# overall_pcb_1_1.net
KiCad netlist of a schematic drawn in EAGLE
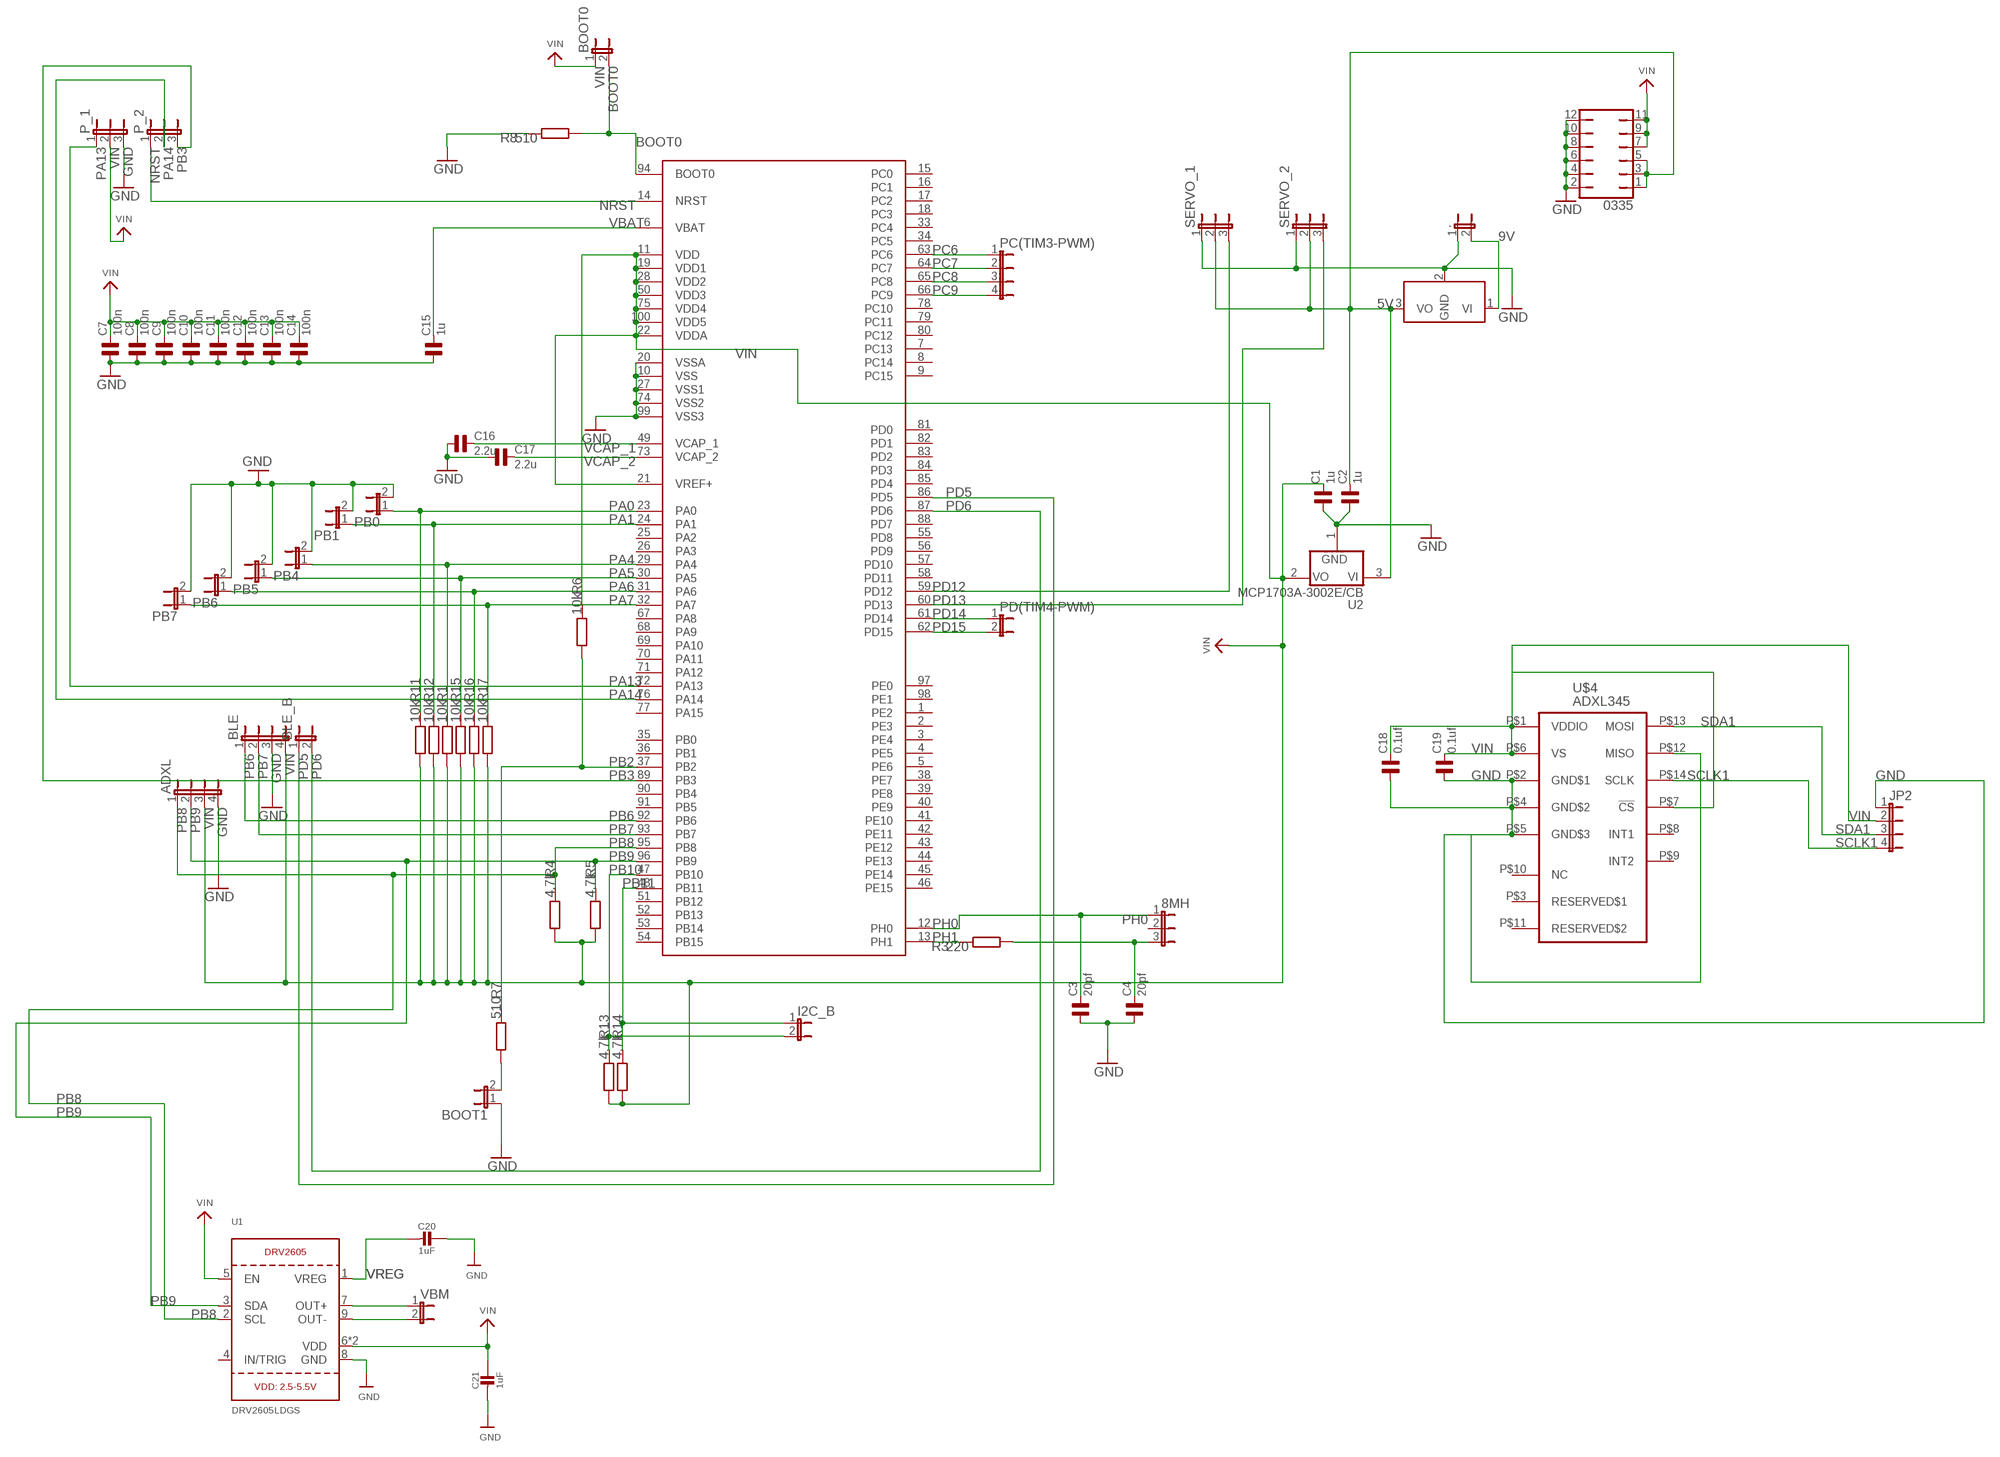
[diagram p0: schematic, sheet 1]

(export (version "E")
  (design (tool "Eeschema 10.0.6"))
  (components
    (comp (ref ".")
      (value "JP1E")
      (footprint "eagle-import:JP1")
      (libsource (lib "eagle-import") (part "JP1E"))
    )
    (comp (ref "8MH")
      (value "JP2E")
      (footprint "eagle-import:JP2")
      (libsource (lib "eagle-import") (part "JP2E"))
    )
    (comp (ref "0335")
      (value "JP6Q")
      (footprint "eagle-import:JP6Q")
      (libsource (lib "eagle-import") (part "JP6Q"))
    )
    (comp (ref "ADXL")
      (value "JP4E")
      (footprint "eagle-import:JP4")
      (libsource (lib "eagle-import") (part "JP4E"))
    )
    (comp (ref "BLE")
      (value "JP4E")
      (footprint "eagle-import:JP4")
      (libsource (lib "eagle-import") (part "JP4E"))
    )
    (comp (ref "BLE_B")
      (value "JP1E")
      (footprint "eagle-import:JP1")
      (libsource (lib "eagle-import") (part "JP1E"))
    )
    (comp (ref "BOOT0")
      (value "JP1E")
      (footprint "eagle-import:JP1")
      (libsource (lib "eagle-import") (part "JP1E"))
    )
    (comp (ref "BOOT1")
      (value "JP1E")
      (footprint "eagle-import:JP1")
      (libsource (lib "eagle-import") (part "JP1E"))
    )
    (comp (ref "C1")
      (value "1u")
      (footprint "eagle-import:0805")
      (libsource (lib "eagle-import") (part "C0805"))
    )
    (comp (ref "C2")
      (value "1u")
      (footprint "eagle-import:0805")
      (libsource (lib "eagle-import") (part "C0805"))
    )
    (comp (ref "C3")
      (value "20pf")
      (footprint "eagle-import:0805")
      (libsource (lib "eagle-import") (part "C0805"))
    )
    (comp (ref "C4")
      (value "20pf")
      (footprint "eagle-import:0805")
      (libsource (lib "eagle-import") (part "C0805"))
    )
    (comp (ref "C7")
      (value "100n")
      (footprint "eagle-import:0805")
      (libsource (lib "eagle-import") (part "C0805"))
    )
    (comp (ref "C8")
      (value "100n")
      (footprint "eagle-import:0805")
      (libsource (lib "eagle-import") (part "C0805"))
    )
    (comp (ref "C9")
      (value "100n")
      (footprint "eagle-import:0805")
      (libsource (lib "eagle-import") (part "C0805"))
    )
    (comp (ref "C10")
      (value "100n")
      (footprint "eagle-import:0805")
      (libsource (lib "eagle-import") (part "C0805"))
    )
    (comp (ref "C11")
      (value "100n")
      (footprint "eagle-import:0805")
      (libsource (lib "eagle-import") (part "C0805"))
    )
    (comp (ref "C12")
      (value "100n")
      (footprint "eagle-import:0805")
      (libsource (lib "eagle-import") (part "C0805"))
    )
    (comp (ref "C13")
      (value "100n")
      (footprint "eagle-import:0805")
      (libsource (lib "eagle-import") (part "C0805"))
    )
    (comp (ref "C14")
      (value "100n")
      (footprint "eagle-import:0805")
      (libsource (lib "eagle-import") (part "C0805"))
    )
    (comp (ref "C15")
      (value "1u")
      (footprint "eagle-import:0805")
      (libsource (lib "eagle-import") (part "C0805"))
    )
    (comp (ref "C16")
      (value "2.2u")
      (footprint "eagle-import:0805")
      (libsource (lib "eagle-import") (part "C0805"))
    )
    (comp (ref "C17")
      (value "2.2u")
      (footprint "eagle-import:0805")
      (libsource (lib "eagle-import") (part "C0805"))
    )
    (comp (ref "C18")
      (value "0.1uf")
      (footprint "eagle-import:0805")
      (libsource (lib "eagle-import") (part "C0805"))
    )
    (comp (ref "C19")
      (value "0.1uf")
      (footprint "eagle-import:0805")
      (libsource (lib "eagle-import") (part "C0805"))
    )
    (comp (ref "C20")
      (value "1uF")
      (footprint "eagle-import:0805-NO")
      (libsource (lib "eagle-import") (part "CAP_CERAMIC0805-NOOUTLINE"))
    )
    (comp (ref "C21")
      (value "1uF")
      (footprint "eagle-import:0805-NO")
      (libsource (lib "eagle-import") (part "CAP_CERAMIC0805-NOOUTLINE"))
    )
    (comp (ref "I2C_B")
      (value "JP1E")
      (footprint "eagle-import:JP1")
      (libsource (lib "eagle-import") (part "JP1E"))
    )
    (comp (ref "JP2")
      (value "JP4E")
      (footprint "eagle-import:JP4")
      (libsource (lib "eagle-import") (part "JP4E"))
    )
    (comp (ref "PB0")
      (value "JP1E")
      (footprint "eagle-import:JP1")
      (libsource (lib "eagle-import") (part "JP1E"))
    )
    (comp (ref "PB1")
      (value "JP1E")
      (footprint "eagle-import:JP1")
      (libsource (lib "eagle-import") (part "JP1E"))
    )
    (comp (ref "PB4")
      (value "JP1E")
      (footprint "eagle-import:JP1")
      (libsource (lib "eagle-import") (part "JP1E"))
    )
    (comp (ref "PB5")
      (value "JP1E")
      (footprint "eagle-import:JP1")
      (libsource (lib "eagle-import") (part "JP1E"))
    )
    (comp (ref "PB6")
      (value "JP1E")
      (footprint "eagle-import:JP1")
      (libsource (lib "eagle-import") (part "JP1E"))
    )
    (comp (ref "PB7")
      (value "JP1E")
      (footprint "eagle-import:JP1")
      (libsource (lib "eagle-import") (part "JP1E"))
    )
    (comp (ref "PC(TIM3-PWM)")
      (value "JP4E")
      (footprint "eagle-import:JP4")
      (libsource (lib "eagle-import") (part "JP4E"))
    )
    (comp (ref "PD(TIM4-PWM)")
      (value "JP1E")
      (footprint "eagle-import:JP1")
      (libsource (lib "eagle-import") (part "JP1E"))
    )
    (comp (ref "P_1")
      (value "JP2E")
      (footprint "eagle-import:JP2")
      (libsource (lib "eagle-import") (part "JP2E"))
    )
    (comp (ref "P_2")
      (value "JP2E")
      (footprint "eagle-import:JP2")
      (libsource (lib "eagle-import") (part "JP2E"))
    )
    (comp (ref "R1")
      (value "10k")
      (footprint "eagle-import:R0805")
      (libsource (lib "eagle-import") (part "R-EU_R0805"))
    )
    (comp (ref "R3")
      (value "220")
      (footprint "eagle-import:R0805")
      (libsource (lib "eagle-import") (part "R-EU_R0805"))
    )
    (comp (ref "R4")
      (value "4.7k")
      (footprint "eagle-import:R0805")
      (libsource (lib "eagle-import") (part "R-EU_R0805"))
    )
    (comp (ref "R5")
      (value "4.7k")
      (footprint "eagle-import:R0805")
      (libsource (lib "eagle-import") (part "R-EU_R0805"))
    )
    (comp (ref "R6")
      (value "10k")
      (footprint "eagle-import:R0805")
      (libsource (lib "eagle-import") (part "R-EU_R0805"))
    )
    (comp (ref "R7")
      (value "510")
      (footprint "eagle-import:R0805")
      (libsource (lib "eagle-import") (part "R-EU_R0805"))
    )
    (comp (ref "R8")
      (value "510")
      (footprint "eagle-import:R0805")
      (libsource (lib "eagle-import") (part "R-EU_R0805"))
    )
    (comp (ref "R11")
      (value "10k")
      (footprint "eagle-import:R0805")
      (libsource (lib "eagle-import") (part "R-EU_R0805"))
    )
    (comp (ref "R12")
      (value "10k")
      (footprint "eagle-import:R0805")
      (libsource (lib "eagle-import") (part "R-EU_R0805"))
    )
    (comp (ref "R13")
      (value "4.7k")
      (footprint "eagle-import:R0805")
      (libsource (lib "eagle-import") (part "R-EU_R0805"))
    )
    (comp (ref "R14")
      (value "4.7k")
      (footprint "eagle-import:R0805")
      (libsource (lib "eagle-import") (part "R-EU_R0805"))
    )
    (comp (ref "R15")
      (value "10k")
      (footprint "eagle-import:R0805")
      (libsource (lib "eagle-import") (part "R-EU_R0805"))
    )
    (comp (ref "R16")
      (value "10k")
      (footprint "eagle-import:R0805")
      (libsource (lib "eagle-import") (part "R-EU_R0805"))
    )
    (comp (ref "R17")
      (value "10k")
      (footprint "eagle-import:R0805")
      (libsource (lib "eagle-import") (part "R-EU_R0805"))
    )
    (comp (ref "SERVO_1")
      (value "JP2E")
      (footprint "eagle-import:JP2")
      (libsource (lib "eagle-import") (part "JP2E"))
    )
    (comp (ref "SERVO_2")
      (value "JP2E")
      (footprint "eagle-import:JP2")
      (libsource (lib "eagle-import") (part "JP2E"))
    )
    (comp (ref "U$1")
      (value "STM32F40XSTM32D40X")
      (footprint "eagle-import:LQFP100")
      (libsource (lib "eagle-import") (part "STM32F40XSTM32D40X"))
    )
    (comp (ref "U$2")
      (value "DCDC_OKI-78SR")
      (footprint "eagle-import:OKI-78SRH")
      (libsource (lib "eagle-import") (part "DCDC_OKI-78SR"))
    )
    (comp (ref "U$4")
      (value "ADXL345")
      (footprint "eagle-import:LGA14")
      (libsource (lib "eagle-import") (part "ADXL345"))
    )
    (comp (ref "U1")
      (value "DRV2605LDGS")
      (footprint "eagle-import:PSOP10")
      (libsource (lib "eagle-import") (part "DRV2605_SOP"))
    )
    (comp (ref "U2")
      (value "MCP1703A-3002E/CB")
      (footprint "eagle-import:SOT23A_MICROCHIP_CB")
      (libsource (lib "eagle-import") (part "MCP170302E/CBA-30"))
    )
    (comp (ref "VBM")
      (value "JP1E")
      (footprint "eagle-import:JP1")
      (libsource (lib "eagle-import") (part "JP1E"))
    )
  )
  (nets
    (net (code "1") (name "/5V") (class "Default")
      (node (ref "0335") (pin "1") (pinfunction "1_1") (pintype "passive"))
      (node (ref "0335") (pin "3") (pinfunction "3_3") (pintype "passive"))
      (node (ref "0335") (pin "5") (pinfunction "5_5") (pintype "passive"))
      (node (ref "C2") (pin "2") (pinfunction "2_2") (pintype "passive"))
      (node (ref "SERVO_1") (pin "2") (pinfunction "2_2") (pintype "passive"))
      (node (ref "SERVO_2") (pin "2") (pinfunction "2_2") (pintype "passive"))
      (node (ref "U$2") (pin "3") (pinfunction "VO_3") (pintype "bidirectional"))
      (node (ref "U2") (pin "3") (pinfunction "VI_3") (pintype "power_in"))
    )
    (net (code "2") (name "/9V") (class "Default")
      (node (ref ".") (pin "2") (pinfunction "2_2") (pintype "passive"))
      (node (ref "U$2") (pin "1") (pinfunction "VI_1") (pintype "bidirectional"))
    )
    (net (code "3") (name "/BOOT0") (class "Default")
      (node (ref "BOOT0") (pin "2") (pinfunction "2_2") (pintype "passive"))
      (node (ref "R8") (pin "1") (pinfunction "1_1") (pintype "passive"))
      (node (ref "U$1") (pin "94") (pinfunction "BOOT0_94") (pintype "bidirectional"))
    )
    (net (code "4") (name "/NRST") (class "Default")
      (node (ref "P_2") (pin "1") (pinfunction "1_1") (pintype "passive"))
      (node (ref "U$1") (pin "14") (pinfunction "NRST_14") (pintype "bidirectional"))
    )
    (net (code "5") (name "/PA0") (class "Default")
      (node (ref "PB0") (pin "1") (pinfunction "1_1") (pintype "passive"))
      (node (ref "R11") (pin "2") (pinfunction "2_2") (pintype "passive"))
      (node (ref "U$1") (pin "23") (pinfunction "PA0_23") (pintype "bidirectional"))
    )
    (net (code "6") (name "/PA1") (class "Default")
      (node (ref "PB1") (pin "1") (pinfunction "1_1") (pintype "passive"))
      (node (ref "R12") (pin "2") (pinfunction "2_2") (pintype "passive"))
      (node (ref "U$1") (pin "24") (pinfunction "PA1_24") (pintype "bidirectional"))
    )
    (net (code "7") (name "/PA4") (class "Default")
      (node (ref "PB4") (pin "1") (pinfunction "1_1") (pintype "passive"))
      (node (ref "R1") (pin "2") (pinfunction "2_2") (pintype "passive"))
      (node (ref "U$1") (pin "29") (pinfunction "PA4_29") (pintype "bidirectional"))
    )
    (net (code "8") (name "/PA5") (class "Default")
      (node (ref "PB5") (pin "1") (pinfunction "1_1") (pintype "passive"))
      (node (ref "R15") (pin "2") (pinfunction "2_2") (pintype "passive"))
      (node (ref "U$1") (pin "30") (pinfunction "PA5_30") (pintype "bidirectional"))
    )
    (net (code "9") (name "/PA6") (class "Default")
      (node (ref "PB6") (pin "1") (pinfunction "1_1") (pintype "passive"))
      (node (ref "R16") (pin "2") (pinfunction "2_2") (pintype "passive"))
      (node (ref "U$1") (pin "31") (pinfunction "PA6_31") (pintype "bidirectional"))
    )
    (net (code "10") (name "/PA7") (class "Default")
      (node (ref "PB7") (pin "1") (pinfunction "1_1") (pintype "passive"))
      (node (ref "R17") (pin "2") (pinfunction "2_2") (pintype "passive"))
      (node (ref "U$1") (pin "32") (pinfunction "PA7_32") (pintype "bidirectional"))
    )
    (net (code "11") (name "/PA13") (class "Default")
      (node (ref "P_1") (pin "1") (pinfunction "1_1") (pintype "passive"))
      (node (ref "U$1") (pin "72") (pinfunction "PA13_72") (pintype "bidirectional"))
    )
    (net (code "12") (name "/PA14") (class "Default")
      (node (ref "P_2") (pin "2") (pinfunction "2_2") (pintype "passive"))
      (node (ref "U$1") (pin "76") (pinfunction "PA14_76") (pintype "bidirectional"))
    )
    (net (code "13") (name "/PB2") (class "Default")
      (node (ref "R6") (pin "1") (pinfunction "1_1") (pintype "passive"))
      (node (ref "R7") (pin "2") (pinfunction "2_2") (pintype "passive"))
      (node (ref "U$1") (pin "37") (pinfunction "PB2_37") (pintype "bidirectional"))
    )
    (net (code "14") (name "/PB3") (class "Default")
      (node (ref "P_2") (pin "3") (pinfunction "3_3") (pintype "passive"))
      (node (ref "U$1") (pin "89") (pinfunction "PB3_89") (pintype "bidirectional"))
    )
    (net (code "15") (name "/PB6") (class "Default")
      (node (ref "BLE") (pin "1") (pinfunction "1_1") (pintype "passive"))
      (node (ref "U$1") (pin "92") (pinfunction "PB6_92") (pintype "bidirectional"))
    )
    (net (code "16") (name "/PB7") (class "Default")
      (node (ref "BLE") (pin "2") (pinfunction "2_2") (pintype "passive"))
      (node (ref "U$1") (pin "93") (pinfunction "PB7_93") (pintype "bidirectional"))
    )
    (net (code "17") (name "/PB8") (class "Default")
      (node (ref "ADXL") (pin "1") (pinfunction "1_1") (pintype "passive"))
      (node (ref "R4") (pin "2") (pinfunction "2_2") (pintype "passive"))
      (node (ref "U$1") (pin "95") (pinfunction "PB8_95") (pintype "bidirectional"))
      (node (ref "U1") (pin "2") (pinfunction "SCL_2") (pintype "input"))
    )
    (net (code "18") (name "/PB9") (class "Default")
      (node (ref "ADXL") (pin "2") (pinfunction "2_2") (pintype "passive"))
      (node (ref "R5") (pin "2") (pinfunction "2_2") (pintype "passive"))
      (node (ref "U$1") (pin "96") (pinfunction "PB9_96") (pintype "bidirectional"))
      (node (ref "U1") (pin "3") (pinfunction "SDA_3") (pintype "bidirectional"))
    )
    (net (code "19") (name "/PB10") (class "Default")
      (node (ref "I2C_B") (pin "2") (pinfunction "2_2") (pintype "passive"))
      (node (ref "R13") (pin "2") (pinfunction "2_2") (pintype "passive"))
      (node (ref "U$1") (pin "47") (pinfunction "PB10_47") (pintype "bidirectional"))
    )
    (net (code "20") (name "/PB11") (class "Default")
      (node (ref "I2C_B") (pin "1") (pinfunction "1_1") (pintype "passive"))
      (node (ref "R14") (pin "2") (pinfunction "2_2") (pintype "passive"))
      (node (ref "U$1") (pin "48") (pinfunction "PB11_48") (pintype "bidirectional"))
    )
    (net (code "21") (name "/PC6") (class "Default")
      (node (ref "PC(TIM3-PWM)") (pin "1") (pinfunction "1_1") (pintype "passive"))
      (node (ref "U$1") (pin "63") (pinfunction "PC6_63") (pintype "bidirectional"))
    )
    (net (code "22") (name "/PC7") (class "Default")
      (node (ref "PC(TIM3-PWM)") (pin "2") (pinfunction "2_2") (pintype "passive"))
      (node (ref "U$1") (pin "64") (pinfunction "PC7_64") (pintype "bidirectional"))
    )
    (net (code "23") (name "/PC8") (class "Default")
      (node (ref "PC(TIM3-PWM)") (pin "3") (pinfunction "3_3") (pintype "passive"))
      (node (ref "U$1") (pin "65") (pinfunction "PC8_65") (pintype "bidirectional"))
    )
    (net (code "24") (name "/PC9") (class "Default")
      (node (ref "PC(TIM3-PWM)") (pin "4") (pinfunction "4_4") (pintype "passive"))
      (node (ref "U$1") (pin "66") (pinfunction "PC9_66") (pintype "bidirectional"))
    )
    (net (code "25") (name "/PD5") (class "Default")
      (node (ref "BLE_B") (pin "1") (pinfunction "1_1") (pintype "passive"))
      (node (ref "U$1") (pin "86") (pinfunction "PD5_86") (pintype "bidirectional"))
    )
    (net (code "26") (name "/PD6") (class "Default")
      (node (ref "BLE_B") (pin "2") (pinfunction "2_2") (pintype "passive"))
      (node (ref "U$1") (pin "87") (pinfunction "PD6_87") (pintype "bidirectional"))
    )
    (net (code "27") (name "/PD12") (class "Default")
      (node (ref "SERVO_1") (pin "3") (pinfunction "3_3") (pintype "passive"))
      (node (ref "U$1") (pin "59") (pinfunction "PD12_59") (pintype "bidirectional"))
    )
    (net (code "28") (name "/PD13") (class "Default")
      (node (ref "SERVO_2") (pin "3") (pinfunction "3_3") (pintype "passive"))
      (node (ref "U$1") (pin "60") (pinfunction "PD13_60") (pintype "bidirectional"))
    )
    (net (code "29") (name "/PD14") (class "Default")
      (node (ref "PD(TIM4-PWM)") (pin "1") (pinfunction "1_1") (pintype "passive"))
      (node (ref "U$1") (pin "61") (pinfunction "PD14_61") (pintype "bidirectional"))
    )
    (net (code "30") (name "/PD15") (class "Default")
      (node (ref "PD(TIM4-PWM)") (pin "2") (pinfunction "2_2") (pintype "passive"))
      (node (ref "U$1") (pin "62") (pinfunction "PD15_62") (pintype "bidirectional"))
    )
    (net (code "31") (name "/PH0") (class "Default")
      (node (ref "8MH") (pin "1") (pinfunction "1_1") (pintype "passive"))
      (node (ref "C3") (pin "2") (pinfunction "2_2") (pintype "passive"))
      (node (ref "U$1") (pin "12") (pinfunction "PH0_12") (pintype "bidirectional"))
    )
    (net (code "32") (name "/PH1") (class "Default")
      (node (ref "R3") (pin "2") (pinfunction "2_2") (pintype "passive"))
      (node (ref "U$1") (pin "13") (pinfunction "PH1_13") (pintype "bidirectional"))
    )
    (net (code "33") (name "/SCLK1") (class "Default")
      (node (ref "JP2") (pin "4") (pinfunction "4_4") (pintype "passive"))
      (node (ref "U$4") (pin "P$14") (pinfunction "SCLK_P$14") (pintype "input"))
    )
    (net (code "34") (name "/SDA1") (class "Default")
      (node (ref "JP2") (pin "3") (pinfunction "3_3") (pintype "passive"))
      (node (ref "U$4") (pin "P$13") (pinfunction "MOSI_P$13") (pintype "input"))
    )
    (net (code "35") (name "/VBAT") (class "Default")
      (node (ref "C15") (pin "2") (pinfunction "2_2") (pintype "passive"))
      (node (ref "U$1") (pin "6") (pinfunction "VBAT_6") (pintype "bidirectional"))
    )
    (net (code "36") (name "/VCAP_1") (class "Default")
      (node (ref "C16") (pin "2") (pinfunction "2_2") (pintype "passive"))
      (node (ref "U$1") (pin "49") (pinfunction "VCAP_1_49") (pintype "bidirectional"))
    )
    (net (code "37") (name "/VCAP_2") (class "Default")
      (node (ref "C17") (pin "2") (pinfunction "2_2") (pintype "passive"))
      (node (ref "U$1") (pin "73") (pinfunction "VCAP_2_73") (pintype "bidirectional"))
    )
    (net (code "38") (name "/VREG") (class "Default")
      (node (ref "C20") (pin "2") (pinfunction "2_2") (pintype "passive"))
      (node (ref "U1") (pin "1") (pinfunction "VREG_1") (pintype "output"))
    )
    (net (code "39") (name "GND") (class "Default")
      (node (ref ".") (pin "1") (pinfunction "1_1") (pintype "passive"))
      (node (ref "0335") (pin "10") (pinfunction "10_10") (pintype "passive"))
      (node (ref "0335") (pin "12") (pinfunction "12_12") (pintype "passive"))
      (node (ref "0335") (pin "2") (pinfunction "2_2") (pintype "passive"))
      (node (ref "0335") (pin "4") (pinfunction "4_4") (pintype "passive"))
      (node (ref "0335") (pin "6") (pinfunction "6_6") (pintype "passive"))
      (node (ref "0335") (pin "8") (pinfunction "8_8") (pintype "passive"))
      (node (ref "ADXL") (pin "4") (pinfunction "4_4") (pintype "passive"))
      (node (ref "BLE") (pin "3") (pinfunction "3_3") (pintype "passive"))
      (node (ref "BOOT1") (pin "1") (pinfunction "1_1") (pintype "passive"))
      (node (ref "C1") (pin "1") (pinfunction "1_1") (pintype "passive"))
      (node (ref "C10") (pin "1") (pinfunction "1_1") (pintype "passive"))
      (node (ref "C11") (pin "1") (pinfunction "1_1") (pintype "passive"))
      (node (ref "C12") (pin "1") (pinfunction "1_1") (pintype "passive"))
      (node (ref "C13") (pin "1") (pinfunction "1_1") (pintype "passive"))
      (node (ref "C14") (pin "1") (pinfunction "1_1") (pintype "passive"))
      (node (ref "C15") (pin "1") (pinfunction "1_1") (pintype "passive"))
      (node (ref "C16") (pin "1") (pinfunction "1_1") (pintype "passive"))
      (node (ref "C17") (pin "1") (pinfunction "1_1") (pintype "passive"))
      (node (ref "C18") (pin "1") (pinfunction "1_1") (pintype "passive"))
      (node (ref "C19") (pin "1") (pinfunction "1_1") (pintype "passive"))
      (node (ref "C2") (pin "1") (pinfunction "1_1") (pintype "passive"))
      (node (ref "C20") (pin "1") (pinfunction "1_1") (pintype "passive"))
      (node (ref "C21") (pin "2") (pinfunction "2_2") (pintype "passive"))
      (node (ref "C3") (pin "1") (pinfunction "1_1") (pintype "passive"))
      (node (ref "C4") (pin "1") (pinfunction "1_1") (pintype "passive"))
      (node (ref "C7") (pin "1") (pinfunction "1_1") (pintype "passive"))
      (node (ref "C8") (pin "1") (pinfunction "1_1") (pintype "passive"))
      (node (ref "C9") (pin "1") (pinfunction "1_1") (pintype "passive"))
      (node (ref "JP2") (pin "1") (pinfunction "1_1") (pintype "passive"))
      (node (ref "PB0") (pin "2") (pinfunction "2_2") (pintype "passive"))
      (node (ref "PB1") (pin "2") (pinfunction "2_2") (pintype "passive"))
      (node (ref "PB4") (pin "2") (pinfunction "2_2") (pintype "passive"))
      (node (ref "PB5") (pin "2") (pinfunction "2_2") (pintype "passive"))
      (node (ref "PB6") (pin "2") (pinfunction "2_2") (pintype "passive"))
      (node (ref "PB7") (pin "2") (pinfunction "2_2") (pintype "passive"))
      (node (ref "P_1") (pin "3") (pinfunction "3_3") (pintype "passive"))
      (node (ref "R8") (pin "2") (pinfunction "2_2") (pintype "passive"))
      (node (ref "SERVO_1") (pin "1") (pinfunction "1_1") (pintype "passive"))
      (node (ref "SERVO_2") (pin "1") (pinfunction "1_1") (pintype "passive"))
      (node (ref "U$1") (pin "10") (pinfunction "VSS_10") (pintype "bidirectional"))
      (node (ref "U$1") (pin "20") (pinfunction "VSSA_20") (pintype "bidirectional"))
      (node (ref "U$1") (pin "27") (pinfunction "VSS1_27") (pintype "bidirectional"))
      (node (ref "U$1") (pin "74") (pinfunction "VSS2_74") (pintype "bidirectional"))
      (node (ref "U$1") (pin "99") (pinfunction "VSS3_99") (pintype "bidirectional"))
      (node (ref "U$2") (pin "2") (pinfunction "GND_2") (pintype "bidirectional"))
      (node (ref "U$4") (pin "P$12") (pinfunction "MISO_P$12") (pintype "output"))
      (node (ref "U$4") (pin "P$2") (pinfunction "GND$1_P$2") (pintype "power_in"))
      (node (ref "U$4") (pin "P$4") (pinfunction "GND$2_P$4") (pintype "power_in"))
      (node (ref "U$4") (pin "P$5") (pinfunction "GND$3_P$5") (pintype "power_in"))
      (node (ref "U1") (pin "8") (pinfunction "GND_8") (pintype "power_in"))
      (node (ref "U2") (pin "1") (pinfunction "GND_1") (pintype "power_in"))
    )
    (net (code "40") (name "Net-(8MH-Pad3)") (class "Default")
      (node (ref "8MH") (pin "3") (pinfunction "3_3") (pintype "passive"))
      (node (ref "C4") (pin "2") (pinfunction "2_2") (pintype "passive"))
      (node (ref "R3") (pin "1") (pinfunction "1_1") (pintype "passive"))
    )
    (net (code "41") (name "Net-(BOOT1-Pad2)") (class "Default")
      (node (ref "BOOT1") (pin "2") (pinfunction "2_2") (pintype "passive"))
      (node (ref "R7") (pin "1") (pinfunction "1_1") (pintype "passive"))
    )
    (net (code "42") (name "Net-(U1-OUT+)") (class "Default")
      (node (ref "U1") (pin "7") (pinfunction "OUT+_7") (pintype "output"))
      (node (ref "VBM") (pin "1") (pinfunction "1_1") (pintype "passive"))
    )
    (net (code "43") (name "Net-(U1-OUT-)") (class "Default")
      (node (ref "U1") (pin "9") (pinfunction "OUT-_9") (pintype "output"))
      (node (ref "VBM") (pin "2") (pinfunction "2_2") (pintype "passive"))
    )
    (net (code "44") (name "VIN") (class "Default")
      (node (ref "0335") (pin "11") (pinfunction "11_11") (pintype "passive"))
      (node (ref "0335") (pin "7") (pinfunction "7_7") (pintype "passive"))
      (node (ref "0335") (pin "9") (pinfunction "9_9") (pintype "passive"))
      (node (ref "ADXL") (pin "3") (pinfunction "3_3") (pintype "passive"))
      (node (ref "BLE") (pin "4") (pinfunction "4_4") (pintype "passive"))
      (node (ref "BOOT0") (pin "1") (pinfunction "1_1") (pintype "passive"))
      (node (ref "C1") (pin "2") (pinfunction "2_2") (pintype "passive"))
      (node (ref "C10") (pin "2") (pinfunction "2_2") (pintype "passive"))
      (node (ref "C11") (pin "2") (pinfunction "2_2") (pintype "passive"))
      (node (ref "C12") (pin "2") (pinfunction "2_2") (pintype "passive"))
      (node (ref "C13") (pin "2") (pinfunction "2_2") (pintype "passive"))
      (node (ref "C14") (pin "2") (pinfunction "2_2") (pintype "passive"))
      (node (ref "C18") (pin "2") (pinfunction "2_2") (pintype "passive"))
      (node (ref "C19") (pin "2") (pinfunction "2_2") (pintype "passive"))
      (node (ref "C21") (pin "1") (pinfunction "1_1") (pintype "passive"))
      (node (ref "C7") (pin "2") (pinfunction "2_2") (pintype "passive"))
      (node (ref "C8") (pin "2") (pinfunction "2_2") (pintype "passive"))
      (node (ref "C9") (pin "2") (pinfunction "2_2") (pintype "passive"))
      (node (ref "JP2") (pin "2") (pinfunction "2_2") (pintype "passive"))
      (node (ref "P_1") (pin "2") (pinfunction "2_2") (pintype "passive"))
      (node (ref "R1") (pin "1") (pinfunction "1_1") (pintype "passive"))
      (node (ref "R11") (pin "1") (pinfunction "1_1") (pintype "passive"))
      (node (ref "R12") (pin "1") (pinfunction "1_1") (pintype "passive"))
      (node (ref "R13") (pin "1") (pinfunction "1_1") (pintype "passive"))
      (node (ref "R14") (pin "1") (pinfunction "1_1") (pintype "passive"))
      (node (ref "R15") (pin "1") (pinfunction "1_1") (pintype "passive"))
      (node (ref "R16") (pin "1") (pinfunction "1_1") (pintype "passive"))
      (node (ref "R17") (pin "1") (pinfunction "1_1") (pintype "passive"))
      (node (ref "R4") (pin "1") (pinfunction "1_1") (pintype "passive"))
      (node (ref "R5") (pin "1") (pinfunction "1_1") (pintype "passive"))
      (node (ref "R6") (pin "2") (pinfunction "2_2") (pintype "passive"))
      (node (ref "U$1") (pin "100") (pinfunction "VDD5_100") (pintype "bidirectional"))
      (node (ref "U$1") (pin "11") (pinfunction "VDD_11") (pintype "bidirectional"))
      (node (ref "U$1") (pin "19") (pinfunction "VDD1_19") (pintype "bidirectional"))
      (node (ref "U$1") (pin "21") (pinfunction "VREF+_21") (pintype "bidirectional"))
      (node (ref "U$1") (pin "22") (pinfunction "VDDA_22") (pintype "bidirectional"))
      (node (ref "U$1") (pin "28") (pinfunction "VDD2_28") (pintype "bidirectional"))
      (node (ref "U$1") (pin "50") (pinfunction "VDD3_50") (pintype "bidirectional"))
      (node (ref "U$1") (pin "75") (pinfunction "VDD4_75") (pintype "bidirectional"))
      (node (ref "U$4") (pin "P$1") (pinfunction "VDDIO_P$1") (pintype "power_in"))
      (node (ref "U$4") (pin "P$6") (pinfunction "VS_P$6") (pintype "power_in"))
      (node (ref "U$4") (pin "P$7") (pinfunction "~{CS}_P$7") (pintype "input"))
      (node (ref "U1") (pin "10") (pinfunction "VDD_10") (pintype "power_in"))
      (node (ref "U1") (pin "5") (pinfunction "EN_5") (pintype "input"))
      (node (ref "U1") (pin "6") (pinfunction "VDD_6") (pintype "power_in"))
      (node (ref "U2") (pin "2") (pinfunction "VO_2") (pintype "passive"))
    )
    (net (code "45") (name "unconnected-(8MH-Pad2)") (class "Default")
      (node (ref "8MH") (pin "2") (pinfunction "2_2") (pintype "passive"))
    )
    (net (code "46") (name "unconnected-(U$1-PA2-Pad25)") (class "Default")
      (node (ref "U$1") (pin "25") (pinfunction "PA2_25") (pintype "bidirectional"))
    )
    (net (code "47") (name "unconnected-(U$1-PA3-Pad26)") (class "Default")
      (node (ref "U$1") (pin "26") (pinfunction "PA3_26") (pintype "bidirectional"))
    )
    (net (code "48") (name "unconnected-(U$1-PA8-Pad67)") (class "Default")
      (node (ref "U$1") (pin "67") (pinfunction "PA8_67") (pintype "bidirectional"))
    )
    (net (code "49") (name "unconnected-(U$1-PA9-Pad68)") (class "Default")
      (node (ref "U$1") (pin "68") (pinfunction "PA9_68") (pintype "bidirectional"))
    )
    (net (code "50") (name "unconnected-(U$1-PA10-Pad69)") (class "Default")
      (node (ref "U$1") (pin "69") (pinfunction "PA10_69") (pintype "bidirectional"))
    )
    (net (code "51") (name "unconnected-(U$1-PA11-Pad70)") (class "Default")
      (node (ref "U$1") (pin "70") (pinfunction "PA11_70") (pintype "bidirectional"))
    )
    (net (code "52") (name "unconnected-(U$1-PA12-Pad71)") (class "Default")
      (node (ref "U$1") (pin "71") (pinfunction "PA12_71") (pintype "bidirectional"))
    )
    (net (code "53") (name "unconnected-(U$1-PA15-Pad77)") (class "Default")
      (node (ref "U$1") (pin "77") (pinfunction "PA15_77") (pintype "bidirectional"))
    )
    (net (code "54") (name "unconnected-(U$1-PB0-Pad35)") (class "Default")
      (node (ref "U$1") (pin "35") (pinfunction "PB0_35") (pintype "bidirectional"))
    )
    (net (code "55") (name "unconnected-(U$1-PB1-Pad36)") (class "Default")
      (node (ref "U$1") (pin "36") (pinfunction "PB1_36") (pintype "bidirectional"))
    )
    (net (code "56") (name "unconnected-(U$1-PB4-Pad90)") (class "Default")
      (node (ref "U$1") (pin "90") (pinfunction "PB4_90") (pintype "bidirectional"))
    )
    (net (code "57") (name "unconnected-(U$1-PB5-Pad91)") (class "Default")
      (node (ref "U$1") (pin "91") (pinfunction "PB5_91") (pintype "bidirectional"))
    )
    (net (code "58") (name "unconnected-(U$1-PB12-Pad51)") (class "Default")
      (node (ref "U$1") (pin "51") (pinfunction "PB12_51") (pintype "bidirectional"))
    )
    (net (code "59") (name "unconnected-(U$1-PB13-Pad52)") (class "Default")
      (node (ref "U$1") (pin "52") (pinfunction "PB13_52") (pintype "bidirectional"))
    )
    (net (code "60") (name "unconnected-(U$1-PB14-Pad53)") (class "Default")
      (node (ref "U$1") (pin "53") (pinfunction "PB14_53") (pintype "bidirectional"))
    )
    (net (code "61") (name "unconnected-(U$1-PB15-Pad54)") (class "Default")
      (node (ref "U$1") (pin "54") (pinfunction "PB15_54") (pintype "bidirectional"))
    )
    (net (code "62") (name "unconnected-(U$1-PC0-Pad15)") (class "Default")
      (node (ref "U$1") (pin "15") (pinfunction "PC0_15") (pintype "bidirectional"))
    )
    (net (code "63") (name "unconnected-(U$1-PC1-Pad16)") (class "Default")
      (node (ref "U$1") (pin "16") (pinfunction "PC1_16") (pintype "bidirectional"))
    )
    (net (code "64") (name "unconnected-(U$1-PC2-Pad17)") (class "Default")
      (node (ref "U$1") (pin "17") (pinfunction "PC2_17") (pintype "bidirectional"))
    )
    (net (code "65") (name "unconnected-(U$1-PC3-Pad18)") (class "Default")
      (node (ref "U$1") (pin "18") (pinfunction "PC3_18") (pintype "bidirectional"))
    )
    (net (code "66") (name "unconnected-(U$1-PC4-Pad33)") (class "Default")
      (node (ref "U$1") (pin "33") (pinfunction "PC4_33") (pintype "bidirectional"))
    )
    (net (code "67") (name "unconnected-(U$1-PC5-Pad34)") (class "Default")
      (node (ref "U$1") (pin "34") (pinfunction "PC5_34") (pintype "bidirectional"))
    )
    (net (code "68") (name "unconnected-(U$1-PC10-Pad78)") (class "Default")
      (node (ref "U$1") (pin "78") (pinfunction "PC10_78") (pintype "bidirectional"))
    )
    (net (code "69") (name "unconnected-(U$1-PC11-Pad79)") (class "Default")
      (node (ref "U$1") (pin "79") (pinfunction "PC11_79") (pintype "bidirectional"))
    )
    (net (code "70") (name "unconnected-(U$1-PC12-Pad80)") (class "Default")
      (node (ref "U$1") (pin "80") (pinfunction "PC12_80") (pintype "bidirectional"))
    )
    (net (code "71") (name "unconnected-(U$1-PC13-Pad7)") (class "Default")
      (node (ref "U$1") (pin "7") (pinfunction "PC13_7") (pintype "bidirectional"))
    )
    (net (code "72") (name "unconnected-(U$1-PC14-Pad8)") (class "Default")
      (node (ref "U$1") (pin "8") (pinfunction "PC14_8") (pintype "bidirectional"))
    )
    (net (code "73") (name "unconnected-(U$1-PC15-Pad9)") (class "Default")
      (node (ref "U$1") (pin "9") (pinfunction "PC15_9") (pintype "bidirectional"))
    )
    (net (code "74") (name "unconnected-(U$1-PD0-Pad81)") (class "Default")
      (node (ref "U$1") (pin "81") (pinfunction "PD0_81") (pintype "bidirectional"))
    )
    (net (code "75") (name "unconnected-(U$1-PD1-Pad82)") (class "Default")
      (node (ref "U$1") (pin "82") (pinfunction "PD1_82") (pintype "bidirectional"))
    )
    (net (code "76") (name "unconnected-(U$1-PD2-Pad83)") (class "Default")
      (node (ref "U$1") (pin "83") (pinfunction "PD2_83") (pintype "bidirectional"))
    )
    (net (code "77") (name "unconnected-(U$1-PD3-Pad84)") (class "Default")
      (node (ref "U$1") (pin "84") (pinfunction "PD3_84") (pintype "bidirectional"))
    )
    (net (code "78") (name "unconnected-(U$1-PD4-Pad85)") (class "Default")
      (node (ref "U$1") (pin "85") (pinfunction "PD4_85") (pintype "bidirectional"))
    )
    (net (code "79") (name "unconnected-(U$1-PD7-Pad88)") (class "Default")
      (node (ref "U$1") (pin "88") (pinfunction "PD7_88") (pintype "bidirectional"))
    )
    (net (code "80") (name "unconnected-(U$1-PD8-Pad55)") (class "Default")
      (node (ref "U$1") (pin "55") (pinfunction "PD8_55") (pintype "bidirectional"))
    )
    (net (code "81") (name "unconnected-(U$1-PD9-Pad56)") (class "Default")
      (node (ref "U$1") (pin "56") (pinfunction "PD9_56") (pintype "bidirectional"))
    )
    (net (code "82") (name "unconnected-(U$1-PD10-Pad57)") (class "Default")
      (node (ref "U$1") (pin "57") (pinfunction "PD10_57") (pintype "bidirectional"))
    )
    (net (code "83") (name "unconnected-(U$1-PD11-Pad58)") (class "Default")
      (node (ref "U$1") (pin "58") (pinfunction "PD11_58") (pintype "bidirectional"))
    )
    (net (code "84") (name "unconnected-(U$1-PE0-Pad97)") (class "Default")
      (node (ref "U$1") (pin "97") (pinfunction "PE0_97") (pintype "bidirectional"))
    )
    (net (code "85") (name "unconnected-(U$1-PE1-Pad98)") (class "Default")
      (node (ref "U$1") (pin "98") (pinfunction "PE1_98") (pintype "bidirectional"))
    )
    (net (code "86") (name "unconnected-(U$1-PE2-Pad1)") (class "Default")
      (node (ref "U$1") (pin "1") (pinfunction "PE2_1") (pintype "bidirectional"))
    )
    (net (code "87") (name "unconnected-(U$1-PE3-Pad2)") (class "Default")
      (node (ref "U$1") (pin "2") (pinfunction "PE3_2") (pintype "bidirectional"))
    )
    (net (code "88") (name "unconnected-(U$1-PE4-Pad3)") (class "Default")
      (node (ref "U$1") (pin "3") (pinfunction "PE4_3") (pintype "bidirectional"))
    )
    (net (code "89") (name "unconnected-(U$1-PE5-Pad4)") (class "Default")
      (node (ref "U$1") (pin "4") (pinfunction "PE5_4") (pintype "bidirectional"))
    )
    (net (code "90") (name "unconnected-(U$1-PE6-Pad5)") (class "Default")
      (node (ref "U$1") (pin "5") (pinfunction "PE6_5") (pintype "bidirectional"))
    )
    (net (code "91") (name "unconnected-(U$1-PE7-Pad38)") (class "Default")
      (node (ref "U$1") (pin "38") (pinfunction "PE7_38") (pintype "bidirectional"))
    )
    (net (code "92") (name "unconnected-(U$1-PE8-Pad39)") (class "Default")
      (node (ref "U$1") (pin "39") (pinfunction "PE8_39") (pintype "bidirectional"))
    )
    (net (code "93") (name "unconnected-(U$1-PE9-Pad40)") (class "Default")
      (node (ref "U$1") (pin "40") (pinfunction "PE9_40") (pintype "bidirectional"))
    )
    (net (code "94") (name "unconnected-(U$1-PE10-Pad41)") (class "Default")
      (node (ref "U$1") (pin "41") (pinfunction "PE10_41") (pintype "bidirectional"))
    )
    (net (code "95") (name "unconnected-(U$1-PE11-Pad42)") (class "Default")
      (node (ref "U$1") (pin "42") (pinfunction "PE11_42") (pintype "bidirectional"))
    )
    (net (code "96") (name "unconnected-(U$1-PE12-Pad43)") (class "Default")
      (node (ref "U$1") (pin "43") (pinfunction "PE12_43") (pintype "bidirectional"))
    )
    (net (code "97") (name "unconnected-(U$1-PE13-Pad44)") (class "Default")
      (node (ref "U$1") (pin "44") (pinfunction "PE13_44") (pintype "bidirectional"))
    )
    (net (code "98") (name "unconnected-(U$1-PE14-Pad45)") (class "Default")
      (node (ref "U$1") (pin "45") (pinfunction "PE14_45") (pintype "bidirectional"))
    )
    (net (code "99") (name "unconnected-(U$1-PE15-Pad46)") (class "Default")
      (node (ref "U$1") (pin "46") (pinfunction "PE15_46") (pintype "bidirectional"))
    )
    (net (code "100") (name "unconnected-(U$4-INT1-PadP$8)") (class "Default")
      (node (ref "U$4") (pin "P$8") (pinfunction "INT1_P$8") (pintype "output"))
    )
    (net (code "101") (name "unconnected-(U$4-INT2-PadP$9)") (class "Default")
      (node (ref "U$4") (pin "P$9") (pinfunction "INT2_P$9") (pintype "output"))
    )
    (net (code "102") (name "unconnected-(U$4-NC-PadP$10)") (class "Default")
      (node (ref "U$4") (pin "P$10") (pinfunction "NC_P$10") (pintype "bidirectional"))
    )
    (net (code "103") (name "unconnected-(U$4-RESERVED$1-PadP$3)") (class "Default")
      (node (ref "U$4") (pin "P$3") (pinfunction "RESERVED$1_P$3") (pintype "bidirectional"))
    )
    (net (code "104") (name "unconnected-(U$4-RESERVED$2-PadP$11)") (class "Default")
      (node (ref "U$4") (pin "P$11") (pinfunction "RESERVED$2_P$11") (pintype "bidirectional"))
    )
    (net (code "105") (name "unconnected-(U1-IN{slash}TRIG-Pad4)") (class "Default")
      (node (ref "U1") (pin "4") (pinfunction "IN/TRIG_4") (pintype "input"))
    )
  )
)
